# PIC795_Brain_Board.net
KiCad netlist of a schematic drawn in EAGLE
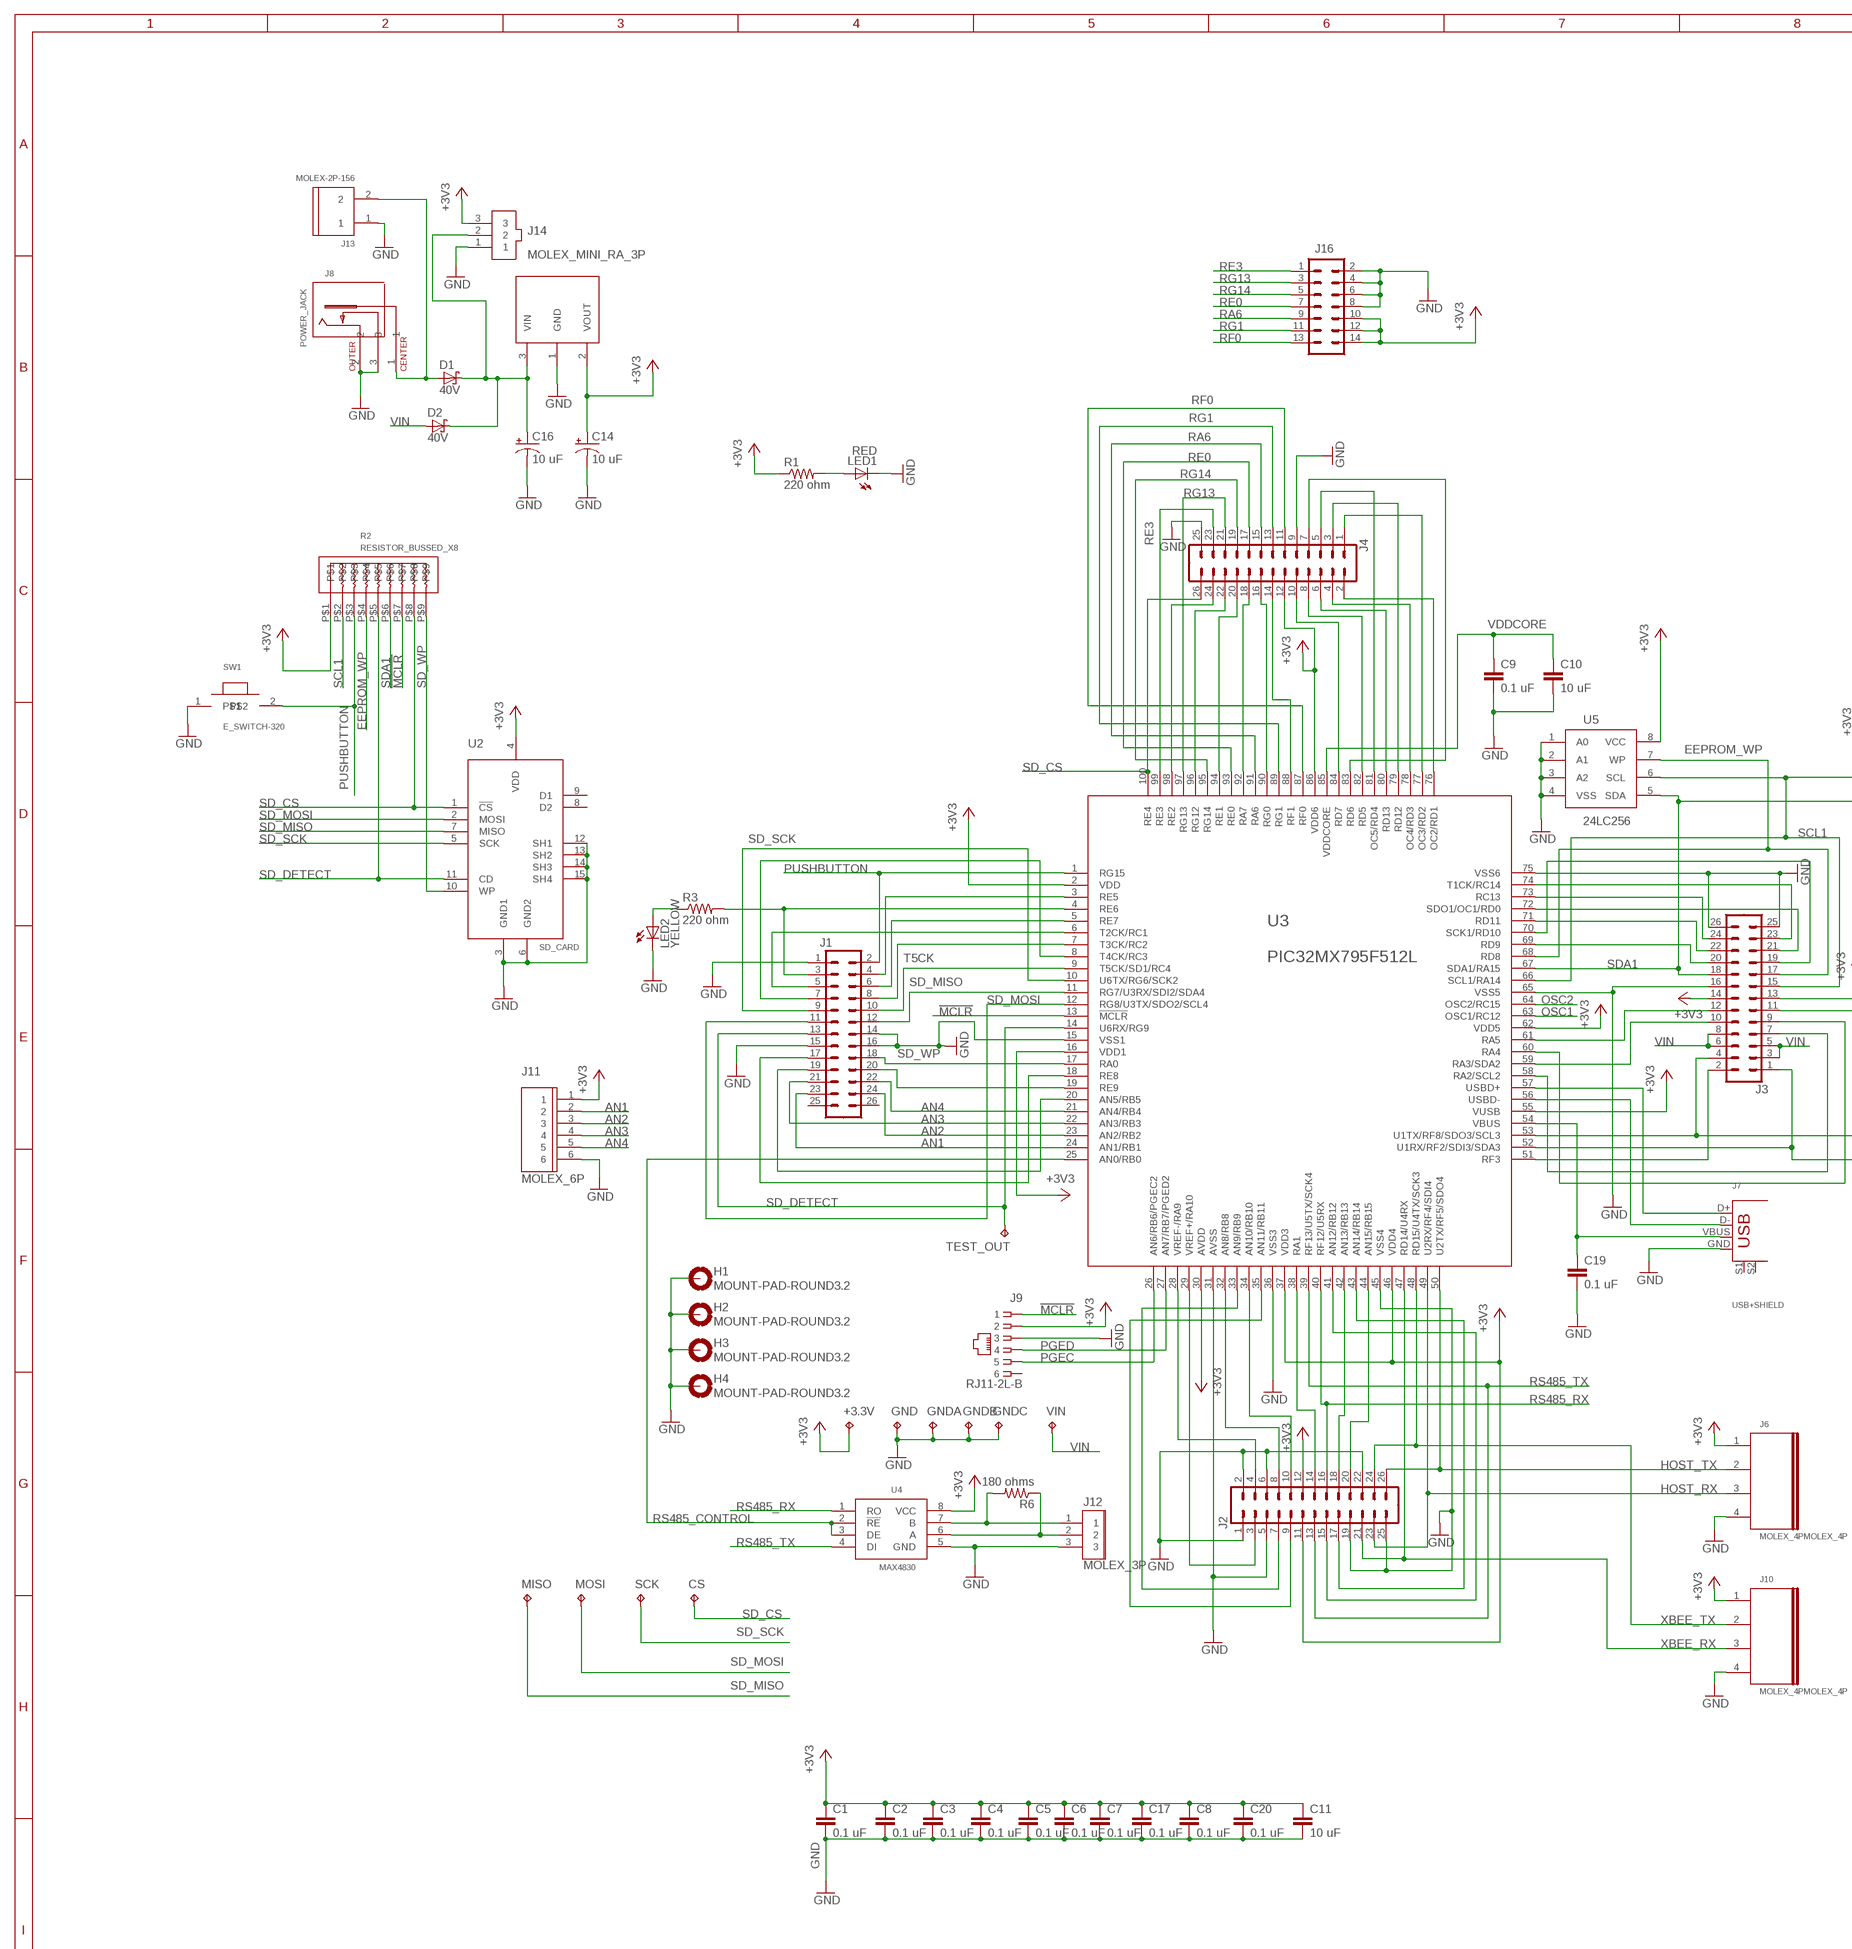
[diagram p0: schematic, sheet 1, part 1 of 2]
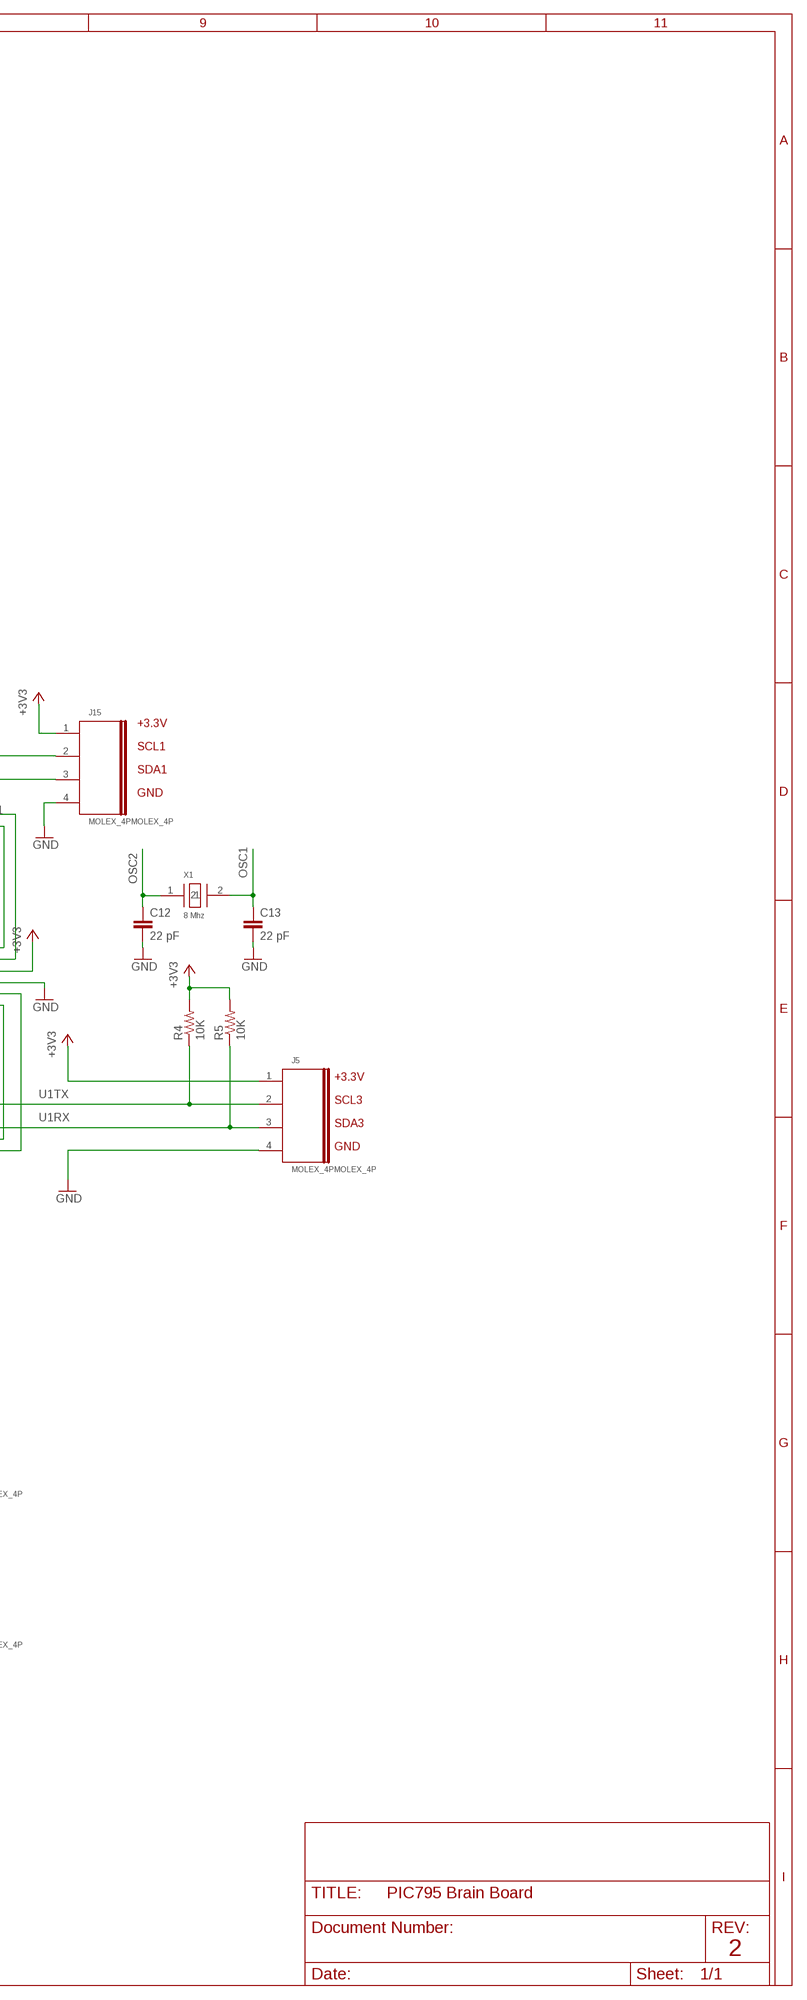
[diagram p1: schematic, sheet 1, part 2 of 2]

(export (version "E")
  (design (tool "Eeschema 10.0.6"))
  (components
    (comp (ref "+3.3V")
      (value "TP")
      (footprint "eagle-import:TESTPAD")
      (libsource (lib "eagle-import") (part "TP"))
    )
    (comp (ref "C1")
      (value "0.1 uF")
      (footprint "eagle-import:1206")
      (libsource (lib "eagle-import") (part "CAP-1206"))
    )
    (comp (ref "C2")
      (value "0.1 uF")
      (footprint "eagle-import:1206")
      (libsource (lib "eagle-import") (part "CAP-1206"))
    )
    (comp (ref "C3")
      (value "0.1 uF")
      (footprint "eagle-import:1206")
      (libsource (lib "eagle-import") (part "CAP-1206"))
    )
    (comp (ref "C4")
      (value "0.1 uF")
      (footprint "eagle-import:1206")
      (libsource (lib "eagle-import") (part "CAP-1206"))
    )
    (comp (ref "C5")
      (value "0.1 uF")
      (footprint "eagle-import:1206")
      (libsource (lib "eagle-import") (part "CAP-1206"))
    )
    (comp (ref "C6")
      (value "0.1 uF")
      (footprint "eagle-import:1206")
      (libsource (lib "eagle-import") (part "CAP-1206"))
    )
    (comp (ref "C7")
      (value "0.1 uF")
      (footprint "eagle-import:1206")
      (libsource (lib "eagle-import") (part "CAP-1206"))
    )
    (comp (ref "C8")
      (value "0.1 uF")
      (footprint "eagle-import:1206")
      (libsource (lib "eagle-import") (part "CAP-1206"))
    )
    (comp (ref "C9")
      (value "0.1 uF")
      (footprint "eagle-import:1206")
      (libsource (lib "eagle-import") (part "CAP-1206"))
    )
    (comp (ref "C10")
      (value "10 uF")
      (footprint "eagle-import:1206")
      (libsource (lib "eagle-import") (part "CAP-1206"))
    )
    (comp (ref "C11")
      (value "10 uF")
      (footprint "eagle-import:1206")
      (libsource (lib "eagle-import") (part "CAP-1206"))
    )
    (comp (ref "C12")
      (value "22 pF")
      (footprint "eagle-import:C0805")
      (libsource (lib "eagle-import") (part "C0805"))
    )
    (comp (ref "C13")
      (value "22 pF")
      (footprint "eagle-import:C0805")
      (libsource (lib "eagle-import") (part "C0805"))
    )
    (comp (ref "C14")
      (value "10 uF")
      (footprint "eagle-import:E2,5-5")
      (libsource (lib "eagle-import") (part "POLCAPE2.5-5"))
    )
    (comp (ref "C16")
      (value "10 uF")
      (footprint "eagle-import:E2,5-5")
      (libsource (lib "eagle-import") (part "POLCAPE2.5-5"))
    )
    (comp (ref "C17")
      (value "0.1 uF")
      (footprint "eagle-import:1206")
      (libsource (lib "eagle-import") (part "CAP-1206"))
    )
    (comp (ref "C19")
      (value "0.1 uF")
      (footprint "eagle-import:C5B2.5")
      (libsource (lib "eagle-import") (part "C5/2.5"))
    )
    (comp (ref "C20")
      (value "0.1 uF")
      (footprint "eagle-import:C5B2.5")
      (libsource (lib "eagle-import") (part "C5/2.5"))
    )
    (comp (ref "CS")
      (value "TP")
      (footprint "eagle-import:TESTPAD")
      (libsource (lib "eagle-import") (part "TP"))
    )
    (comp (ref "D1")
      (value "40V")
      (footprint "eagle-import:DO41-7.6")
      (libsource (lib "eagle-import") (part "1N5817-B"))
    )
    (comp (ref "D2")
      (value "40V")
      (footprint "eagle-import:DO41-7.6")
      (libsource (lib "eagle-import") (part "1N5817-B"))
    )
    (comp (ref "GND")
      (value "TP")
      (footprint "eagle-import:TESTPAD")
      (libsource (lib "eagle-import") (part "TP"))
    )
    (comp (ref "GNDA")
      (value "TP")
      (footprint "eagle-import:TESTPAD")
      (libsource (lib "eagle-import") (part "TP"))
    )
    (comp (ref "GNDB")
      (value "TP")
      (footprint "eagle-import:TESTPAD")
      (libsource (lib "eagle-import") (part "TP"))
    )
    (comp (ref "GNDC")
      (value "TP")
      (footprint "eagle-import:TESTPAD")
      (libsource (lib "eagle-import") (part "TP"))
    )
    (comp (ref "H1")
      (value "MOUNT-PAD-ROUND3.2")
      (footprint "eagle-import:3,2-PAD")
      (libsource (lib "eagle-import") (part "MOUNT-PAD-ROUND3.2"))
    )
    (comp (ref "H2")
      (value "MOUNT-PAD-ROUND3.2")
      (footprint "eagle-import:3,2-PAD")
      (libsource (lib "eagle-import") (part "MOUNT-PAD-ROUND3.2"))
    )
    (comp (ref "H3")
      (value "MOUNT-PAD-ROUND3.2")
      (footprint "eagle-import:3,2-PAD")
      (libsource (lib "eagle-import") (part "MOUNT-PAD-ROUND3.2"))
    )
    (comp (ref "H4")
      (value "MOUNT-PAD-ROUND3.2")
      (footprint "eagle-import:3,2-PAD")
      (libsource (lib "eagle-import") (part "MOUNT-PAD-ROUND3.2"))
    )
    (comp (ref "J1")
      (value "M13X22X13")
      (footprint "eagle-import:2X13")
      (libsource (lib "eagle-import") (part "M13X22X13"))
    )
    (comp (ref "J2")
      (value "M13X22X13")
      (footprint "eagle-import:2X13")
      (libsource (lib "eagle-import") (part "M13X22X13"))
    )
    (comp (ref "J3")
      (value "M13X22X13")
      (footprint "eagle-import:2X13")
      (libsource (lib "eagle-import") (part "M13X22X13"))
    )
    (comp (ref "J4")
      (value "M13X22X13")
      (footprint "eagle-import:2X13")
      (libsource (lib "eagle-import") (part "M13X22X13"))
    )
    (comp (ref "J5")
      (value "MOLEX_4PMOLEX_4P")
      (footprint "eagle-import:MOLEX_4P")
      (libsource (lib "eagle-import") (part "MOLEX_4PMOLEX_4P"))
    )
    (comp (ref "J6")
      (value "MOLEX_4PMOLEX_4P")
      (footprint "eagle-import:MOLEX_4P")
      (libsource (lib "eagle-import") (part "MOLEX_4PMOLEX_4P"))
    )
    (comp (ref "J7")
      (value "USB+SHIELD")
      (footprint "eagle-import:USB-B-PTH")
      (libsource (lib "eagle-import") (part "USB+SHIELD"))
    )
    (comp (ref "J8")
      (value "POWER_JACK")
      (footprint "eagle-import:POWER_JACK_PJ-202A")
      (libsource (lib "eagle-import") (part "POWER_JACK"))
    )
    (comp (ref "J9")
      (value "RJ11-2L-B")
      (footprint "eagle-import:RJ11-NO_SHIELD")
      (fields (field (name "MF") "TYCO ELECTRONICS"))
      (libsource (lib "eagle-import") (part "RJ11-2L-B"))
    )
    (comp (ref "J10")
      (value "MOLEX_4PMOLEX_4P")
      (footprint "eagle-import:MOLEX_4P")
      (libsource (lib "eagle-import") (part "MOLEX_4PMOLEX_4P"))
    )
    (comp (ref "J11")
      (value "MOLEX_6P")
      (footprint "eagle-import:MOLEX_6P_SLIM")
      (libsource (lib "eagle-import") (part "MOLEX_6P"))
    )
    (comp (ref "J12")
      (value "MOLEX_3P")
      (footprint "eagle-import:MOLEX_3P")
      (libsource (lib "eagle-import") (part "MOLEX_3P"))
    )
    (comp (ref "J13")
      (value "MOLEX-2P-156")
      (footprint "eagle-import:MOLEX-156-2P")
      (libsource (lib "eagle-import") (part "MOLEX-2P-156"))
    )
    (comp (ref "J14")
      (value "MOLEX_MINI_RA_3P")
      (footprint "eagle-import:MOLEX_MINI_RA_3P")
      (libsource (lib "eagle-import") (part "MOLEX_MINI_RA_3P"))
    )
    (comp (ref "J15")
      (value "MOLEX_4PMOLEX_4P")
      (footprint "eagle-import:MOLEX_4P")
      (libsource (lib "eagle-import") (part "MOLEX_4PMOLEX_4P"))
    )
    (comp (ref "J16")
      (value "CONNECTOR_DUAL_ROW_14")
      (footprint "eagle-import:2X7")
      (libsource (lib "eagle-import") (part "CONNECTOR_DUAL_ROW_14"))
    )
    (comp (ref "LED1")
      (value "RED")
      (footprint "eagle-import:LED5MM")
      (libsource (lib "eagle-import") (part "LED5MM"))
    )
    (comp (ref "LED2")
      (value "YELLOW")
      (footprint "eagle-import:LED5MM")
      (libsource (lib "eagle-import") (part "LED5MM"))
    )
    (comp (ref "MISO")
      (value "TP")
      (footprint "eagle-import:TESTPAD")
      (libsource (lib "eagle-import") (part "TP"))
    )
    (comp (ref "MOSI")
      (value "TP")
      (footprint "eagle-import:TESTPAD")
      (libsource (lib "eagle-import") (part "TP"))
    )
    (comp (ref "R1")
      (value "220 ohm")
      (footprint "eagle-import:1_4_WATT")
      (libsource (lib "eagle-import") (part "RESISTOR0207/12"))
    )
    (comp (ref "R2")
      (value "RESISTOR_BUSSED_X8")
      (footprint "eagle-import:RESISTOR_BUSSED")
      (libsource (lib "eagle-import") (part "RESISTOR_BUSSED_X8"))
    )
    (comp (ref "R3")
      (value "220 ohm")
      (footprint "eagle-import:1_4_WATT")
      (libsource (lib "eagle-import") (part "RESISTOR0207/12"))
    )
    (comp (ref "R4")
      (value "10K")
      (footprint "eagle-import:1_4_WATT")
      (libsource (lib "eagle-import") (part "RESISTOR0207/12"))
    )
    (comp (ref "R5")
      (value "10K")
      (footprint "eagle-import:1_4_WATT")
      (libsource (lib "eagle-import") (part "RESISTOR0207/12"))
    )
    (comp (ref "R6")
      (value "180 ohms")
      (footprint "eagle-import:0204_7")
      (libsource (lib "eagle-import") (part "RESISTOR0204/7"))
    )
    (comp (ref "SCK")
      (value "TP")
      (footprint "eagle-import:TESTPAD")
      (libsource (lib "eagle-import") (part "TP"))
    )
    (comp (ref "SW1")
      (value "E_SWITCH-320")
      (footprint "eagle-import:E_SWITCH_320")
      (libsource (lib "eagle-import") (part "E_SWITCH-320"))
    )
    (comp (ref "TEST_OUT")
      (value "TP")
      (footprint "eagle-import:TESTPAD")
      (libsource (lib "eagle-import") (part "TP"))
    )
    (comp (ref "U1")
      (value "REGULATOR_LD1086_LDO")
      (footprint "eagle-import:D2PAK")
      (libsource (lib "eagle-import") (part "REGULATOR_LD1086_LDO"))
    )
    (comp (ref "U2")
      (value "SD_CARD")
      (footprint "eagle-import:SD_CARD_TE_2041021")
      (libsource (lib "eagle-import") (part "SD_CARD"))
    )
    (comp (ref "U3")
      (value "PIC32MX795F512L")
      (footprint "eagle-import:TQFP-100-14X14MM")
      (libsource (lib "eagle-import") (part "PIC32MX795F512L"))
    )
    (comp (ref "U4")
      (value "MAX4830")
      (footprint "eagle-import:SOICN")
      (libsource (lib "eagle-import") (part "MAX485"))
    )
    (comp (ref "U5")
      (value "24LC256")
      (footprint "eagle-import:DIL08")
      (libsource (lib "eagle-import") (part "EEPROM_24LC256"))
    )
    (comp (ref "VIN")
      (value "TP")
      (footprint "eagle-import:TESTPAD")
      (libsource (lib "eagle-import") (part "TP"))
    )
    (comp (ref "X1")
      (value "8 Mhz")
      (footprint "eagle-import:CRYSTAL-SMD")
      (libsource (lib "eagle-import") (part "CRYSTAL-SMD"))
    )
  )
  (nets
    (net (code "1") (name "+3V3") (class "Default")
      (node (ref "+3.3V") (pin "P$1") (pinfunction "TP_P$1") (pintype "input"))
      (node (ref "C1") (pin "A") (pinfunction "1_A") (pintype "passive"))
      (node (ref "C11") (pin "A") (pinfunction "1_A") (pintype "passive"))
      (node (ref "C14") (pin "+") (pinfunction "+_+") (pintype "passive"))
      (node (ref "C17") (pin "A") (pinfunction "1_A") (pintype "passive"))
      (node (ref "C2") (pin "A") (pinfunction "1_A") (pintype "passive"))
      (node (ref "C20") (pin "1") (pinfunction "1_1") (pintype "passive"))
      (node (ref "C3") (pin "A") (pinfunction "1_A") (pintype "passive"))
      (node (ref "C4") (pin "A") (pinfunction "1_A") (pintype "passive"))
      (node (ref "C5") (pin "A") (pinfunction "1_A") (pintype "passive"))
      (node (ref "C6") (pin "A") (pinfunction "1_A") (pintype "passive"))
      (node (ref "C7") (pin "A") (pinfunction "1_A") (pintype "passive"))
      (node (ref "C8") (pin "A") (pinfunction "1_A") (pintype "passive"))
      (node (ref "J10") (pin "1") (pinfunction "1_1") (pintype "bidirectional"))
      (node (ref "J11") (pin "1") (pinfunction "1_1") (pintype "bidirectional"))
      (node (ref "J14") (pin "3") (pinfunction "3_3") (pintype "bidirectional"))
      (node (ref "J15") (pin "1") (pinfunction "1_1") (pintype "bidirectional"))
      (node (ref "J16") (pin "10") (pinfunction "10_10") (pintype "passive"))
      (node (ref "J16") (pin "12") (pinfunction "12_12") (pintype "passive"))
      (node (ref "J16") (pin "14") (pinfunction "14_14") (pintype "passive"))
      (node (ref "J2") (pin "11") (pinfunction "11_11") (pintype "passive"))
      (node (ref "J2") (pin "12") (pinfunction "12_12") (pintype "passive"))
      (node (ref "J3") (pin "13") (pinfunction "13_13") (pintype "passive"))
      (node (ref "J3") (pin "14") (pinfunction "14_14") (pintype "passive"))
      (node (ref "J4") (pin "12") (pinfunction "12_12") (pintype "passive"))
      (node (ref "J5") (pin "1") (pinfunction "1_1") (pintype "bidirectional"))
      (node (ref "J6") (pin "1") (pinfunction "1_1") (pintype "bidirectional"))
      (node (ref "J9") (pin "2") (pinfunction "2_2") (pintype "passive"))
      (node (ref "R1") (pin "1") (pinfunction "1_1") (pintype "passive"))
      (node (ref "R2") (pin "P$1") (pinfunction "P$1_P$1") (pintype "bidirectional"))
      (node (ref "R4") (pin "2") (pinfunction "2_2") (pintype "passive"))
      (node (ref "R5") (pin "2") (pinfunction "2_2") (pintype "passive"))
      (node (ref "U1") (pin "2") (pinfunction "VOUT_2") (pintype "bidirectional"))
      (node (ref "U2") (pin "4") (pinfunction "VDD_4") (pintype "bidirectional"))
      (node (ref "U3") (pin "16") (pinfunction "VDD1_16") (pintype "bidirectional"))
      (node (ref "U3") (pin "2") (pinfunction "VDD_2") (pintype "bidirectional"))
      (node (ref "U3") (pin "30") (pinfunction "AVDD_30") (pintype "bidirectional"))
      (node (ref "U3") (pin "37") (pinfunction "VDD3_37") (pintype "bidirectional"))
      (node (ref "U3") (pin "46") (pinfunction "VDD4_46") (pintype "bidirectional"))
      (node (ref "U3") (pin "55") (pinfunction "VUSB_55") (pintype "bidirectional"))
      (node (ref "U3") (pin "62") (pinfunction "VDD5_62") (pintype "bidirectional"))
      (node (ref "U3") (pin "86") (pinfunction "VDD6_86") (pintype "bidirectional"))
      (node (ref "U4") (pin "8") (pinfunction "VCC_8") (pintype "power_in"))
      (node (ref "U5") (pin "8") (pinfunction "VCC_8") (pintype "bidirectional"))
    )
    (net (code "2") (name "/AN1") (class "Default")
      (node (ref "J1") (pin "23") (pinfunction "23_23") (pintype "passive"))
      (node (ref "J11") (pin "2") (pinfunction "2_2") (pintype "bidirectional"))
      (node (ref "U3") (pin "24") (pinfunction "AN1/RB1_24") (pintype "bidirectional"))
    )
    (net (code "3") (name "/AN2") (class "Default")
      (node (ref "J1") (pin "24") (pinfunction "24_24") (pintype "passive"))
      (node (ref "J11") (pin "3") (pinfunction "3_3") (pintype "bidirectional"))
      (node (ref "U3") (pin "23") (pinfunction "AN2/RB2_23") (pintype "bidirectional"))
    )
    (net (code "4") (name "/AN3") (class "Default")
      (node (ref "J1") (pin "21") (pinfunction "21_21") (pintype "passive"))
      (node (ref "J11") (pin "4") (pinfunction "4_4") (pintype "bidirectional"))
      (node (ref "U3") (pin "22") (pinfunction "AN3/RB3_22") (pintype "bidirectional"))
    )
    (net (code "5") (name "/AN4") (class "Default")
      (node (ref "J1") (pin "22") (pinfunction "22_22") (pintype "passive"))
      (node (ref "J11") (pin "5") (pinfunction "5_5") (pintype "bidirectional"))
      (node (ref "U3") (pin "21") (pinfunction "AN4/RB4_21") (pintype "bidirectional"))
    )
    (net (code "6") (name "/EEPROM_WP") (class "Default")
      (node (ref "J3") (pin "17") (pinfunction "17_17") (pintype "passive"))
      (node (ref "R2") (pin "P$4") (pinfunction "P$4_P$4") (pintype "bidirectional"))
      (node (ref "U3") (pin "68") (pinfunction "RD8_68") (pintype "bidirectional"))
      (node (ref "U5") (pin "7") (pinfunction "WP_7") (pintype "bidirectional"))
    )
    (net (code "7") (name "/HOST_RX") (class "Default")
      (node (ref "J2") (pin "23") (pinfunction "23_23") (pintype "passive"))
      (node (ref "J6") (pin "3") (pinfunction "3_3") (pintype "bidirectional"))
      (node (ref "U3") (pin "49") (pinfunction "U2RX/RF4/SDI4_49") (pintype "bidirectional"))
    )
    (net (code "8") (name "/HOST_TX") (class "Default")
      (node (ref "J2") (pin "26") (pinfunction "26_26") (pintype "passive"))
      (node (ref "J6") (pin "2") (pinfunction "2_2") (pintype "bidirectional"))
      (node (ref "U3") (pin "50") (pinfunction "U2TX/RF5/SDO4_50") (pintype "bidirectional"))
    )
    (net (code "9") (name "/OSC1") (class "Default")
      (node (ref "C13") (pin "1") (pinfunction "1_1") (pintype "passive"))
      (node (ref "U3") (pin "63") (pinfunction "OSC1/RC12_63") (pintype "bidirectional"))
      (node (ref "X1") (pin "2") (pinfunction "2_2") (pintype "bidirectional"))
    )
    (net (code "10") (name "/OSC2") (class "Default")
      (node (ref "C12") (pin "1") (pinfunction "1_1") (pintype "passive"))
      (node (ref "U3") (pin "64") (pinfunction "OSC2/RC15_64") (pintype "bidirectional"))
      (node (ref "X1") (pin "1") (pinfunction "1_1") (pintype "bidirectional"))
    )
    (net (code "11") (name "/PGEC") (class "Default")
      (node (ref "J9") (pin "5") (pinfunction "5_5") (pintype "passive"))
      (node (ref "U3") (pin "26") (pinfunction "AN6/RB6/PGEC2_26") (pintype "bidirectional"))
    )
    (net (code "12") (name "/PGED") (class "Default")
      (node (ref "J9") (pin "4") (pinfunction "4_4") (pintype "passive"))
      (node (ref "U3") (pin "27") (pinfunction "AN7/RB7/PGED2_27") (pintype "bidirectional"))
    )
    (net (code "13") (name "/PUSHBUTTON") (class "Default")
      (node (ref "J1") (pin "2") (pinfunction "2_2") (pintype "passive"))
      (node (ref "R2") (pin "P$3") (pinfunction "P$3_P$3") (pintype "bidirectional"))
      (node (ref "SW1") (pin "2") (pinfunction "P$2_2") (pintype "bidirectional"))
      (node (ref "U3") (pin "1") (pinfunction "RG15_1") (pintype "bidirectional"))
    )
    (net (code "14") (name "/RA6") (class "Default")
      (node (ref "J16") (pin "9") (pinfunction "9_9") (pintype "passive"))
      (node (ref "J4") (pin "15") (pinfunction "15_15") (pintype "passive"))
      (node (ref "U3") (pin "91") (pinfunction "RA6_91") (pintype "bidirectional"))
    )
    (net (code "15") (name "/RE0") (class "Default")
      (node (ref "J16") (pin "7") (pinfunction "7_7") (pintype "passive"))
      (node (ref "J4") (pin "17") (pinfunction "17_17") (pintype "passive"))
      (node (ref "U3") (pin "93") (pinfunction "RE0_93") (pintype "bidirectional"))
    )
    (net (code "16") (name "/RE3") (class "Default")
      (node (ref "J16") (pin "1") (pinfunction "1_1") (pintype "passive"))
      (node (ref "J4") (pin "23") (pinfunction "23_23") (pintype "passive"))
      (node (ref "U3") (pin "99") (pinfunction "RE3_99") (pintype "bidirectional"))
    )
    (net (code "17") (name "/RF0") (class "Default")
      (node (ref "J16") (pin "13") (pinfunction "13_13") (pintype "passive"))
      (node (ref "J4") (pin "11") (pinfunction "11_11") (pintype "passive"))
      (node (ref "U3") (pin "87") (pinfunction "RF0_87") (pintype "bidirectional"))
    )
    (net (code "18") (name "/RG1") (class "Default")
      (node (ref "J16") (pin "11") (pinfunction "11_11") (pintype "passive"))
      (node (ref "J4") (pin "13") (pinfunction "13_13") (pintype "passive"))
      (node (ref "U3") (pin "89") (pinfunction "RG1_89") (pintype "bidirectional"))
    )
    (net (code "19") (name "/RG13") (class "Default")
      (node (ref "J16") (pin "3") (pinfunction "3_3") (pintype "passive"))
      (node (ref "J4") (pin "21") (pinfunction "21_21") (pintype "passive"))
      (node (ref "U3") (pin "97") (pinfunction "RG13_97") (pintype "bidirectional"))
    )
    (net (code "20") (name "/RG14") (class "Default")
      (node (ref "J16") (pin "5") (pinfunction "5_5") (pintype "passive"))
      (node (ref "J4") (pin "19") (pinfunction "19_19") (pintype "passive"))
      (node (ref "U3") (pin "95") (pinfunction "RG14_95") (pintype "bidirectional"))
    )
    (net (code "21") (name "/RS485_CONTROL") (class "Default")
      (node (ref "U3") (pin "25") (pinfunction "AN0/RB0_25") (pintype "bidirectional"))
      (node (ref "U4") (pin "2") (pinfunction "~{RE}_2") (pintype "input"))
      (node (ref "U4") (pin "3") (pinfunction "DE_3") (pintype "input"))
    )
    (net (code "22") (name "/RS485_RX") (class "Default")
      (node (ref "J2") (pin "16") (pinfunction "16_16") (pintype "passive"))
      (node (ref "U3") (pin "40") (pinfunction "RF12/U5RX_40") (pintype "bidirectional"))
      (node (ref "U4") (pin "1") (pinfunction "RO_1") (pintype "output"))
    )
    (net (code "23") (name "/RS485_TX") (class "Default")
      (node (ref "J2") (pin "13") (pinfunction "13_13") (pintype "passive"))
      (node (ref "U3") (pin "39") (pinfunction "RF13/U5TX/SCK4_39") (pintype "bidirectional"))
      (node (ref "U4") (pin "4") (pinfunction "DI_4") (pintype "input"))
    )
    (net (code "24") (name "/SCL1") (class "Default")
      (node (ref "J15") (pin "2") (pinfunction "2_2") (pintype "bidirectional"))
      (node (ref "J3") (pin "15") (pinfunction "15_15") (pintype "passive"))
      (node (ref "R2") (pin "P$2") (pinfunction "P$2_P$2") (pintype "bidirectional"))
      (node (ref "U3") (pin "66") (pinfunction "SCL1/RA14_66") (pintype "bidirectional"))
      (node (ref "U5") (pin "6") (pinfunction "SCL_6") (pintype "bidirectional"))
    )
    (net (code "25") (name "/SDA1") (class "Default")
      (node (ref "J15") (pin "3") (pinfunction "3_3") (pintype "bidirectional"))
      (node (ref "J3") (pin "18") (pinfunction "18_18") (pintype "passive"))
      (node (ref "R2") (pin "P$6") (pinfunction "P$6_P$6") (pintype "bidirectional"))
      (node (ref "U3") (pin "67") (pinfunction "SDA1/RA15_67") (pintype "bidirectional"))
      (node (ref "U5") (pin "5") (pinfunction "SDA_5") (pintype "bidirectional"))
    )
    (net (code "26") (name "/SD_CS") (class "Default")
      (node (ref "CS") (pin "P$1") (pinfunction "TP_P$1") (pintype "input"))
      (node (ref "J4") (pin "26") (pinfunction "26_26") (pintype "passive"))
      (node (ref "R2") (pin "P$8") (pinfunction "P$8_P$8") (pintype "bidirectional"))
      (node (ref "U2") (pin "1") (pinfunction "~{CS}_1") (pintype "bidirectional"))
      (node (ref "U3") (pin "100") (pinfunction "RE4_100") (pintype "bidirectional"))
    )
    (net (code "27") (name "/SD_DETECT") (class "Default")
      (node (ref "J1") (pin "13") (pinfunction "13_13") (pintype "passive"))
      (node (ref "R2") (pin "P$5") (pinfunction "P$5_P$5") (pintype "bidirectional"))
      (node (ref "TEST_OUT") (pin "P$1") (pinfunction "TP_P$1") (pintype "input"))
      (node (ref "U2") (pin "11") (pinfunction "CD_11") (pintype "bidirectional"))
      (node (ref "U3") (pin "14") (pinfunction "U6RX/RG9_14") (pintype "bidirectional"))
    )
    (net (code "28") (name "/SD_MISO") (class "Default")
      (node (ref "J1") (pin "12") (pinfunction "12_12") (pintype "passive"))
      (node (ref "MISO") (pin "P$1") (pinfunction "TP_P$1") (pintype "input"))
      (node (ref "U2") (pin "7") (pinfunction "MISO_7") (pintype "bidirectional"))
      (node (ref "U3") (pin "11") (pinfunction "RG7/U3RX/SDI2/SDA4_11") (pintype "bidirectional"))
    )
    (net (code "29") (name "/SD_MOSI") (class "Default")
      (node (ref "J1") (pin "11") (pinfunction "11_11") (pintype "passive"))
      (node (ref "MOSI") (pin "P$1") (pinfunction "TP_P$1") (pintype "input"))
      (node (ref "U2") (pin "2") (pinfunction "MOSI_2") (pintype "bidirectional"))
      (node (ref "U3") (pin "12") (pinfunction "RG8/U3TX/SDO2/SCL4_12") (pintype "bidirectional"))
    )
    (net (code "30") (name "/SD_SCK") (class "Default")
      (node (ref "J1") (pin "9") (pinfunction "9_9") (pintype "passive"))
      (node (ref "SCK") (pin "P$1") (pinfunction "TP_P$1") (pintype "input"))
      (node (ref "U2") (pin "5") (pinfunction "SCK_5") (pintype "bidirectional"))
      (node (ref "U3") (pin "10") (pinfunction "U6TX/RG6/SCK2_10") (pintype "bidirectional"))
    )
    (net (code "31") (name "/SD_WP") (class "Default")
      (node (ref "J1") (pin "18") (pinfunction "18_18") (pintype "passive"))
      (node (ref "R2") (pin "P$9") (pinfunction "P$9_P$9") (pintype "bidirectional"))
      (node (ref "U2") (pin "10") (pinfunction "WP_10") (pintype "bidirectional"))
      (node (ref "U3") (pin "17") (pinfunction "RA0_17") (pintype "bidirectional"))
    )
    (net (code "32") (name "/T5CK") (class "Default")
      (node (ref "J1") (pin "10") (pinfunction "10_10") (pintype "passive"))
      (node (ref "U3") (pin "9") (pinfunction "T5CK/SD1/RC4_9") (pintype "bidirectional"))
    )
    (net (code "33") (name "/U1RX") (class "Default")
      (node (ref "J3") (pin "1") (pinfunction "1_1") (pintype "passive"))
      (node (ref "J5") (pin "3") (pinfunction "3_3") (pintype "bidirectional"))
      (node (ref "R5") (pin "1") (pinfunction "1_1") (pintype "passive"))
      (node (ref "U3") (pin "52") (pinfunction "U1RX/RF2/SDI3/SDA3_52") (pintype "bidirectional"))
    )
    (net (code "34") (name "/U1TX") (class "Default")
      (node (ref "J3") (pin "4") (pinfunction "4_4") (pintype "passive"))
      (node (ref "J5") (pin "2") (pinfunction "2_2") (pintype "bidirectional"))
      (node (ref "R4") (pin "1") (pinfunction "1_1") (pintype "passive"))
      (node (ref "U3") (pin "53") (pinfunction "U1TX/RF8/SDO3/SCL3_53") (pintype "bidirectional"))
    )
    (net (code "35") (name "/VDDCORE") (class "Default")
      (node (ref "C10") (pin "A") (pinfunction "1_A") (pintype "passive"))
      (node (ref "C9") (pin "A") (pinfunction "1_A") (pintype "passive"))
      (node (ref "U3") (pin "85") (pinfunction "VDDCORE_85") (pintype "bidirectional"))
    )
    (net (code "36") (name "/VIN") (class "Default")
      (node (ref "D2") (pin "A") (pinfunction "A_A") (pintype "passive"))
      (node (ref "J3") (pin "3") (pinfunction "3_3") (pintype "passive"))
      (node (ref "J3") (pin "5") (pinfunction "5_5") (pintype "passive"))
      (node (ref "J3") (pin "6") (pinfunction "6_6") (pintype "passive"))
      (node (ref "J3") (pin "8") (pinfunction "8_8") (pintype "passive"))
      (node (ref "VIN") (pin "P$1") (pinfunction "TP_P$1") (pintype "input"))
    )
    (net (code "37") (name "/XBEE_RX") (class "Default")
      (node (ref "J10") (pin "3") (pinfunction "3_3") (pintype "bidirectional"))
      (node (ref "J2") (pin "21") (pinfunction "21_21") (pintype "passive"))
      (node (ref "U3") (pin "47") (pinfunction "RD14/U4RX_47") (pintype "bidirectional"))
    )
    (net (code "38") (name "/XBEE_TX") (class "Default")
      (node (ref "J10") (pin "2") (pinfunction "2_2") (pintype "bidirectional"))
      (node (ref "J2") (pin "24") (pinfunction "24_24") (pintype "passive"))
      (node (ref "U3") (pin "48") (pinfunction "RD15/U4TX/SCK3_48") (pintype "bidirectional"))
    )
    (net (code "39") (name "/~{MCLR}") (class "Default")
      (node (ref "J9") (pin "1") (pinfunction "1_1") (pintype "passive"))
      (node (ref "R2") (pin "P$7") (pinfunction "P$7_P$7") (pintype "bidirectional"))
      (node (ref "U3") (pin "13") (pinfunction "~{MCLR}_13") (pintype "bidirectional"))
    )
    (net (code "40") (name "GND") (class "Default")
      (node (ref "C1") (pin "C") (pinfunction "2_C") (pintype "passive"))
      (node (ref "C10") (pin "C") (pinfunction "2_C") (pintype "passive"))
      (node (ref "C11") (pin "C") (pinfunction "2_C") (pintype "passive"))
      (node (ref "C12") (pin "2") (pinfunction "2_2") (pintype "passive"))
      (node (ref "C13") (pin "2") (pinfunction "2_2") (pintype "passive"))
      (node (ref "C14") (pin "-") (pinfunction "-_-") (pintype "passive"))
      (node (ref "C16") (pin "-") (pinfunction "-_-") (pintype "passive"))
      (node (ref "C17") (pin "C") (pinfunction "2_C") (pintype "passive"))
      (node (ref "C19") (pin "2") (pinfunction "2_2") (pintype "passive"))
      (node (ref "C2") (pin "C") (pinfunction "2_C") (pintype "passive"))
      (node (ref "C20") (pin "2") (pinfunction "2_2") (pintype "passive"))
      (node (ref "C3") (pin "C") (pinfunction "2_C") (pintype "passive"))
      (node (ref "C4") (pin "C") (pinfunction "2_C") (pintype "passive"))
      (node (ref "C5") (pin "C") (pinfunction "2_C") (pintype "passive"))
      (node (ref "C6") (pin "C") (pinfunction "2_C") (pintype "passive"))
      (node (ref "C7") (pin "C") (pinfunction "2_C") (pintype "passive"))
      (node (ref "C8") (pin "C") (pinfunction "2_C") (pintype "passive"))
      (node (ref "C9") (pin "C") (pinfunction "2_C") (pintype "passive"))
      (node (ref "GND") (pin "P$1") (pinfunction "TP_P$1") (pintype "input"))
      (node (ref "GNDA") (pin "P$1") (pinfunction "TP_P$1") (pintype "input"))
      (node (ref "GNDB") (pin "P$1") (pinfunction "TP_P$1") (pintype "input"))
      (node (ref "GNDC") (pin "P$1") (pinfunction "TP_P$1") (pintype "input"))
      (node (ref "H1") (pin "B3,2") (pinfunction "MOUNT_B3,2") (pintype "passive"))
      (node (ref "H2") (pin "B3,2") (pinfunction "MOUNT_B3,2") (pintype "passive"))
      (node (ref "H3") (pin "B3,2") (pinfunction "MOUNT_B3,2") (pintype "passive"))
      (node (ref "H4") (pin "B3,2") (pinfunction "MOUNT_B3,2") (pintype "passive"))
      (node (ref "J1") (pin "1") (pinfunction "1_1") (pintype "passive"))
      (node (ref "J1") (pin "14") (pinfunction "14_14") (pintype "passive"))
      (node (ref "J1") (pin "15") (pinfunction "15_15") (pintype "passive"))
      (node (ref "J1") (pin "16") (pinfunction "16_16") (pintype "passive"))
      (node (ref "J10") (pin "4") (pinfunction "4_4") (pintype "bidirectional"))
      (node (ref "J11") (pin "6") (pinfunction "6_6") (pintype "bidirectional"))
      (node (ref "J12") (pin "3") (pinfunction "3_3") (pintype "bidirectional"))
      (node (ref "J13") (pin "1") (pinfunction "1_1") (pintype "bidirectional"))
      (node (ref "J14") (pin "1") (pinfunction "1_1") (pintype "bidirectional"))
      (node (ref "J15") (pin "4") (pinfunction "4_4") (pintype "bidirectional"))
      (node (ref "J16") (pin "2") (pinfunction "2_2") (pintype "passive"))
      (node (ref "J16") (pin "4") (pinfunction "4_4") (pintype "passive"))
      (node (ref "J16") (pin "6") (pinfunction "6_6") (pintype "passive"))
      (node (ref "J16") (pin "8") (pinfunction "8_8") (pintype "passive"))
      (node (ref "J2") (pin "1") (pinfunction "1_1") (pintype "passive"))
      (node (ref "J2") (pin "19") (pinfunction "19_19") (pintype "passive"))
      (node (ref "J2") (pin "2") (pinfunction "2_2") (pintype "passive"))
      (node (ref "J2") (pin "22") (pinfunction "22_22") (pintype "passive"))
      (node (ref "J2") (pin "25") (pinfunction "25_25") (pintype "passive"))
      (node (ref "J2") (pin "5") (pinfunction "5_5") (pintype "passive"))
      (node (ref "J2") (pin "6") (pinfunction "6_6") (pintype "passive"))
      (node (ref "J3") (pin "11") (pinfunction "11_11") (pintype "passive"))
      (node (ref "J3") (pin "16") (pinfunction "16_16") (pintype "passive"))
      (node (ref "J3") (pin "25") (pinfunction "25_25") (pintype "passive"))
      (node (ref "J3") (pin "26") (pinfunction "26_26") (pintype "passive"))
      (node (ref "J4") (pin "25") (pinfunction "25_25") (pintype "passive"))
      (node (ref "J4") (pin "9") (pinfunction "9_9") (pintype "passive"))
      (node (ref "J5") (pin "4") (pinfunction "4_4") (pintype "bidirectional"))
      (node (ref "J6") (pin "4") (pinfunction "4_4") (pintype "bidirectional"))
      (node (ref "J7") (pin "GND") (pinfunction "GND_GND") (pintype "bidirectional"))
      (node (ref "J8") (pin "2") (pinfunction "2_2") (pintype "bidirectional"))
      (node (ref "J8") (pin "3") (pinfunction "3_3") (pintype "bidirectional"))
      (node (ref "J9") (pin "3") (pinfunction "3_3") (pintype "passive"))
      (node (ref "LED1") (pin "K") (pinfunction "C_K") (pintype "passive"))
      (node (ref "LED2") (pin "K") (pinfunction "C_K") (pintype "passive"))
      (node (ref "SW1") (pin "1") (pinfunction "P$1_1") (pintype "bidirectional"))
      (node (ref "U1") (pin "1") (pinfunction "GND_1") (pintype "bidirectional"))
      (node (ref "U2") (pin "12") (pinfunction "SH1_12") (pintype "bidirectional"))
      (node (ref "U2") (pin "13") (pinfunction "SH2_13") (pintype "bidirectional"))
      (node (ref "U2") (pin "14") (pinfunction "SH3_14") (pintype "bidirectional"))
      (node (ref "U2") (pin "15") (pinfunction "SH4_15") (pintype "bidirectional"))
      (node (ref "U2") (pin "3") (pinfunction "GND1_3") (pintype "bidirectional"))
      (node (ref "U2") (pin "6") (pinfunction "GND2_6") (pintype "bidirectional"))
      (node (ref "U3") (pin "15") (pinfunction "VSS1_15") (pintype "bidirectional"))
      (node (ref "U3") (pin "31") (pinfunction "AVSS_31") (pintype "bidirectional"))
      (node (ref "U3") (pin "36") (pinfunction "VSS3_36") (pintype "bidirectional"))
      (node (ref "U3") (pin "45") (pinfunction "VSS4_45") (pintype "bidirectional"))
      (node (ref "U3") (pin "65") (pinfunction "VSS5_65") (pintype "bidirectional"))
      (node (ref "U3") (pin "75") (pinfunction "VSS6_75") (pintype "bidirectional"))
      (node (ref "U4") (pin "5") (pinfunction "GND_5") (pintype "power_in"))
      (node (ref "U5") (pin "1") (pinfunction "A0_1") (pintype "bidirectional"))
      (node (ref "U5") (pin "2") (pinfunction "A1_2") (pintype "bidirectional"))
      (node (ref "U5") (pin "3") (pinfunction "A2_3") (pintype "bidirectional"))
      (node (ref "U5") (pin "4") (pinfunction "VSS_4") (pintype "bidirectional"))
    )
    (net (code "41") (name "Net-(D1-PadA)") (class "Default")
      (node (ref "D1") (pin "A") (pinfunction "A_A") (pintype "passive"))
      (node (ref "J13") (pin "2") (pinfunction "2_2") (pintype "bidirectional"))
      (node (ref "J8") (pin "1") (pinfunction "1_1") (pintype "bidirectional"))
    )
    (net (code "42") (name "Net-(LED1-PadA)") (class "Default")
      (node (ref "LED1") (pin "A") (pinfunction "A_A") (pintype "passive"))
      (node (ref "R1") (pin "2") (pinfunction "2_2") (pintype "passive"))
    )
    (net (code "43") (name "Net-(LED2-PadA)") (class "Default")
      (node (ref "LED2") (pin "A") (pinfunction "A_A") (pintype "passive"))
      (node (ref "R3") (pin "1") (pinfunction "1_1") (pintype "passive"))
    )
    (net (code "44") (name "Net-(U1-VIN)") (class "Default")
      (node (ref "C16") (pin "+") (pinfunction "+_+") (pintype "passive"))
      (node (ref "D1") (pin "C") (pinfunction "C_C") (pintype "passive"))
      (node (ref "D2") (pin "C") (pinfunction "C_C") (pintype "passive"))
      (node (ref "J14") (pin "2") (pinfunction "2_2") (pintype "bidirectional"))
      (node (ref "U1") (pin "3") (pinfunction "VIN_3") (pintype "bidirectional"))
    )
    (net (code "45") (name "Net-(U3-AN5{slash}RB5)") (class "Default")
      (node (ref "J1") (pin "19") (pinfunction "19_19") (pintype "passive"))
      (node (ref "U3") (pin "20") (pinfunction "AN5/RB5_20") (pintype "bidirectional"))
    )
    (net (code "46") (name "Net-(U3-AN8{slash}RB8)") (class "Default")
      (node (ref "J2") (pin "8") (pinfunction "8_8") (pintype "passive"))
      (node (ref "U3") (pin "32") (pinfunction "AN8/RB8_32") (pintype "bidirectional"))
    )
    (net (code "47") (name "Net-(U3-AN9{slash}RB9)") (class "Default")
      (node (ref "J2") (pin "7") (pinfunction "7_7") (pintype "passive"))
      (node (ref "U3") (pin "33") (pinfunction "AN9/RB9_33") (pintype "bidirectional"))
    )
    (net (code "48") (name "Net-(U3-AN10{slash}RB10)") (class "Default")
      (node (ref "J2") (pin "10") (pinfunction "10_10") (pintype "passive"))
      (node (ref "U3") (pin "34") (pinfunction "AN10/RB10_34") (pintype "bidirectional"))
    )
    (net (code "49") (name "Net-(U3-AN11{slash}RB11)") (class "Default")
      (node (ref "J2") (pin "9") (pinfunction "9_9") (pintype "passive"))
      (node (ref "U3") (pin "35") (pinfunction "AN11/RB11_35") (pintype "bidirectional"))
    )
    (net (code "50") (name "Net-(U3-AN12{slash}RB12)") (class "Default")
      (node (ref "J2") (pin "15") (pinfunction "15_15") (pintype "passive"))
      (node (ref "U3") (pin "41") (pinfunction "AN12/RB12_41") (pintype "bidirectional"))
    )
    (net (code "51") (name "Net-(U3-AN13{slash}RB13)") (class "Default")
      (node (ref "J2") (pin "18") (pinfunction "18_18") (pintype "passive"))
      (node (ref "U3") (pin "42") (pinfunction "AN13/RB13_42") (pintype "bidirectional"))
    )
    (net (code "52") (name "Net-(U3-AN14{slash}RB14)") (class "Default")
      (node (ref "J2") (pin "17") (pinfunction "17_17") (pintype "passive"))
      (node (ref "U3") (pin "43") (pinfunction "AN14/RB14_43") (pintype "bidirectional"))
    )
    (net (code "53") (name "Net-(U3-AN15{slash}RB15)") (class "Default")
      (node (ref "J2") (pin "20") (pinfunction "20_20") (pintype "passive"))
      (node (ref "U3") (pin "44") (pinfunction "AN15/RB15_44") (pintype "bidirectional"))
    )
    (net (code "54") (name "Net-(U3-OC2{slash}RD1)") (class "Default")
      (node (ref "J4") (pin "2") (pinfunction "2_2") (pintype "passive"))
      (node (ref "U3") (pin "76") (pinfunction "OC2/RD1_76") (pintype "bidirectional"))
    )
    (net (code "55") (name "Net-(U3-OC3{slash}RD2)") (class "Default")
      (node (ref "J4") (pin "1") (pinfunction "1_1") (pintype "passive"))
      (node (ref "U3") (pin "77") (pinfunction "OC3/RD2_77") (pintype "bidirectional"))
    )
    (net (code "56") (name "Net-(U3-OC4{slash}RD3)") (class "Default")
      (node (ref "J4") (pin "4") (pinfunction "4_4") (pintype "passive"))
      (node (ref "U3") (pin "78") (pinfunction "OC4/RD3_78") (pintype "bidirectional"))
    )
    (net (code "57") (name "Net-(U3-OC5{slash}RD4)") (class "Default")
      (node (ref "J4") (pin "5") (pinfunction "5_5") (pintype "passive"))
      (node (ref "U3") (pin "81") (pinfunction "OC5/RD4_81") (pintype "bidirectional"))
    )
    (net (code "58") (name "Net-(U3-RA1)") (class "Default")
      (node (ref "J2") (pin "14") (pinfunction "14_14") (pintype "passive"))
      (node (ref "U3") (pin "38") (pinfunction "RA1_38") (pintype "bidirectional"))
    )
    (net (code "59") (name "Net-(U3-RA2{slash}SCL2)") (class "Default")
      (node (ref "J3") (pin "7") (pinfunction "7_7") (pintype "passive"))
      (node (ref "U3") (pin "58") (pinfunction "RA2/SCL2_58") (pintype "bidirectional"))
    )
    (net (code "60") (name "Net-(U3-RA3{slash}SDA2)") (class "Default")
      (node (ref "J3") (pin "10") (pinfunction "10_10") (pintype "passive"))
      (node (ref "U3") (pin "59") (pinfunction "RA3/SDA2_59") (pintype "bidirectional"))
    )
    (net (code "61") (name "Net-(U3-RA4)") (class "Default")
      (node (ref "J3") (pin "9") (pinfunction "9_9") (pintype "passive"))
      (node (ref "U3") (pin "60") (pinfunction "RA4_60") (pintype "bidirectional"))
    )
    (net (code "62") (name "Net-(U3-RA5)") (class "Default")
      (node (ref "J3") (pin "12") (pinfunction "12_12") (pintype "passive"))
      (node (ref "U3") (pin "61") (pinfunction "RA5_61") (pintype "bidirectional"))
    )
    (net (code "63") (name "Net-(U3-RA7)") (class "Default")
      (node (ref "J4") (pin "18") (pinfunction "18_18") (pintype "passive"))
      (node (ref "U3") (pin "92") (pinfunction "RA7_92") (pintype "bidirectional"))
    )
    (net (code "64") (name "Net-(U3-RC13)") (class "Default")
      (node (ref "J3") (pin "24") (pinfunction "24_24") (pintype "passive"))
      (node (ref "U3") (pin "73") (pinfunction "RC13_73") (pintype "bidirectional"))
    )
    (net (code "65") (name "Net-(U3-RD5)") (class "Default")
      (node (ref "J4") (pin "8") (pinfunction "8_8") (pintype "passive"))
      (node (ref "U3") (pin "82") (pinfunction "RD5_82") (pintype "bidirectional"))
    )
    (net (code "66") (name "Net-(U3-RD6)") (class "Default")
      (node (ref "J4") (pin "7") (pinfunction "7_7") (pintype "passive"))
      (node (ref "U3") (pin "83") (pinfunction "RD6_83") (pintype "bidirectional"))
    )
    (net (code "67") (name "Net-(U3-RD7)") (class "Default")
      (node (ref "J4") (pin "10") (pinfunction "10_10") (pintype "passive"))
      (node (ref "U3") (pin "84") (pinfunction "RD7_84") (pintype "bidirectional"))
    )
    (net (code "68") (name "Net-(U3-RD9)") (class "Default")
      (node (ref "J3") (pin "20") (pinfunction "20_20") (pintype "passive"))
      (node (ref "U3") (pin "69") (pinfunction "RD9_69") (pintype "bidirectional"))
    )
    (net (code "69") (name "Net-(U3-RD11)") (class "Default")
      (node (ref "J3") (pin "22") (pinfunction "22_22") (pintype "passive"))
      (node (ref "U3") (pin "71") (pinfunction "RD11_71") (pintype "bidirectional"))
    )
    (net (code "70") (name "Net-(U3-RD12)") (class "Default")
      (node (ref "J4") (pin "3") (pinfunction "3_3") (pintype "passive"))
      (node (ref "U3") (pin "79") (pinfunction "RD12_79") (pintype "bidirectional"))
    )
    (net (code "71") (name "Net-(U3-RD13)") (class "Default")
      (node (ref "J4") (pin "6") (pinfunction "6_6") (pintype "passive"))
      (node (ref "U3") (pin "80") (pinfunction "RD13_80") (pintype "bidirectional"))
    )
    (net (code "72") (name "Net-(U3-RE1)") (class "Default")
      (node (ref "J4") (pin "20") (pinfunction "20_20") (pintype "passive"))
      (node (ref "U3") (pin "94") (pinfunction "RE1_94") (pintype "bidirectional"))
    )
    (net (code "73") (name "Net-(U3-RE2)") (class "Default")
      (node (ref "J4") (pin "24") (pinfunction "24_24") (pintype "passive"))
      (node (ref "U3") (pin "98") (pinfunction "RE2_98") (pintype "bidirectional"))
    )
    (net (code "74") (name "Net-(U3-RE5)") (class "Default")
      (node (ref "J1") (pin "4") (pinfunction "4_4") (pintype "passive"))
      (node (ref "U3") (pin "3") (pinfunction "RE5_3") (pintype "bidirectional"))
    )
    (net (code "75") (name "Net-(U3-RE6)") (class "Default")
      (node (ref "J1") (pin "3") (pinfunction "3_3") (pintype "passive"))
      (node (ref "R3") (pin "2") (pinfunction "2_2") (pintype "passive"))
      (node (ref "U3") (pin "4") (pinfunction "RE6_4") (pintype "bidirectional"))
    )
    (net (code "76") (name "Net-(U3-RE7)") (class "Default")
      (node (ref "J1") (pin "6") (pinfunction "6_6") (pintype "passive"))
      (node (ref "U3") (pin "5") (pinfunction "RE7_5") (pintype "bidirectional"))
    )
    (net (code "77") (name "Net-(U3-RE8)") (class "Default")
      (node (ref "J1") (pin "17") (pinfunction "17_17") (pintype "passive"))
      (node (ref "U3") (pin "18") (pinfunction "RE8_18") (pintype "bidirectional"))
    )
    (net (code "78") (name "Net-(U3-RE9)") (class "Default")
      (node (ref "J1") (pin "20") (pinfunction "20_20") (pintype "passive"))
      (node (ref "U3") (pin "19") (pinfunction "RE9_19") (pintype "bidirectional"))
    )
    (net (code "79") (name "Net-(U3-RF1)") (class "Default")
      (node (ref "J4") (pin "14") (pinfunction "14_14") (pintype "passive"))
      (node (ref "U3") (pin "88") (pinfunction "RF1_88") (pintype "bidirectional"))
    )
    (net (code "80") (name "Net-(U3-RF3)") (class "Default")
      (node (ref "J3") (pin "2") (pinfunction "2_2") (pintype "passive"))
      (node (ref "U3") (pin "51") (pinfunction "RF3_51") (pintype "bidirectional"))
    )
    (net (code "81") (name "Net-(U3-RG0)") (class "Default")
      (node (ref "J4") (pin "16") (pinfunction "16_16") (pintype "passive"))
      (node (ref "U3") (pin "90") (pinfunction "RG0_90") (pintype "bidirectional"))
    )
    (net (code "82") (name "Net-(U3-RG12)") (class "Default")
      (node (ref "J4") (pin "22") (pinfunction "22_22") (pintype "passive"))
      (node (ref "U3") (pin "96") (pinfunction "RG12_96") (pintype "bidirectional"))
    )
    (net (code "83") (name "Net-(U3-SCK1{slash}RD10)") (class "Default")
      (node (ref "J3") (pin "19") (pinfunction "19_19") (pintype "passive"))
      (node (ref "U3") (pin "70") (pinfunction "SCK1/RD10_70") (pintype "bidirectional"))
    )
    (net (code "84") (name "Net-(U3-SDO1{slash}OC1{slash}RD0)") (class "Default")
      (node (ref "J3") (pin "21") (pinfunction "21_21") (pintype "passive"))
      (node (ref "U3") (pin "72") (pinfunction "SDO1/OC1/RD0_72") (pintype "bidirectional"))
    )
    (net (code "85") (name "Net-(U3-T1CK{slash}RC14)") (class "Default")
      (node (ref "J3") (pin "23") (pinfunction "23_23") (pintype "passive"))
      (node (ref "U3") (pin "74") (pinfunction "T1CK/RC14_74") (pintype "bidirectional"))
    )
    (net (code "86") (name "Net-(U3-T2CK{slash}RC1)") (class "Default")
      (node (ref "J1") (pin "5") (pinfunction "5_5") (pintype "passive"))
      (node (ref "U3") (pin "6") (pinfunction "T2CK/RC1_6") (pintype "bidirectional"))
    )
    (net (code "87") (name "Net-(U3-T3CK{slash}RC2)") (class "Default")
      (node (ref "J1") (pin "8") (pinfunction "8_8") (pintype "passive"))
      (node (ref "U3") (pin "7") (pinfunction "T3CK/RC2_7") (pintype "bidirectional"))
    )
    (net (code "88") (name "Net-(U3-T4CK{slash}RC3)") (class "Default")
      (node (ref "J1") (pin "7") (pinfunction "7_7") (pintype "passive"))
      (node (ref "U3") (pin "8") (pinfunction "T4CK/RC3_8") (pintype "bidirectional"))
    )
    (net (code "89") (name "Net-(U3-USBD+)") (class "Default")
      (node (ref "J7") (pin "D+") (pinfunction "D+_D+") (pintype "bidirectional"))
      (node (ref "U3") (pin "57") (pinfunction "USBD+_57") (pintype "bidirectional"))
    )
    (net (code "90") (name "Net-(U3-USBD-)") (class "Default")
      (node (ref "J7") (pin "D-") (pinfunction "D-_D-") (pintype "bidirectional"))
      (node (ref "U3") (pin "56") (pinfunction "USBD-_56") (pintype "bidirectional"))
    )
    (net (code "91") (name "Net-(U3-VBUS)") (class "Default")
      (node (ref "C19") (pin "1") (pinfunction "1_1") (pintype "passive"))
      (node (ref "J7") (pin "VBUS") (pinfunction "VBUS_VBUS") (pintype "bidirectional"))
      (node (ref "U3") (pin "54") (pinfunction "VBUS_54") (pintype "bidirectional"))
    )
    (net (code "92") (name "Net-(U3-VREF+{slash}RA10)") (class "Default")
      (node (ref "J2") (pin "3") (pinfunction "3_3") (pintype "passive"))
      (node (ref "U3") (pin "29") (pinfunction "VREF+/RA10_29") (pintype "bidirectional"))
    )
    (net (code "93") (name "Net-(U3-VREF-{slash}RA9)") (class "Default")
      (node (ref "J2") (pin "4") (pinfunction "4_4") (pintype "passive"))
      (node (ref "U3") (pin "28") (pinfunction "VREF-/RA9_28") (pintype "bidirectional"))
    )
    (net (code "94") (name "Net-(U4-A)") (class "Default")
      (node (ref "J12") (pin "2") (pinfunction "2_2") (pintype "bidirectional"))
      (node (ref "R6") (pin "1") (pinfunction "1_1") (pintype "passive"))
      (node (ref "U4") (pin "6") (pinfunction "A_6") (pintype "bidirectional"))
    )
    (net (code "95") (name "Net-(U4-B)") (class "Default")
      (node (ref "J12") (pin "1") (pinfunction "1_1") (pintype "bidirectional"))
      (node (ref "R6") (pin "2") (pinfunction "2_2") (pintype "passive"))
      (node (ref "U4") (pin "7") (pinfunction "B_7") (pintype "bidirectional"))
    )
    (net (code "96") (name "unconnected-(J1-Pad25)") (class "Default")
      (node (ref "J1") (pin "25") (pinfunction "25_25") (pintype "passive"))
    )
    (net (code "97") (name "unconnected-(J1-Pad26)") (class "Default")
      (node (ref "J1") (pin "26") (pinfunction "26_26") (pintype "passive"))
    )
    (net (code "98") (name "unconnected-(J7-PadS1)") (class "Default")
      (node (ref "J7") (pin "S1") (pinfunction "S1_S1") (pintype "bidirectional"))
    )
    (net (code "99") (name "unconnected-(J7-PadS2)") (class "Default")
      (node (ref "J7") (pin "S2") (pinfunction "S2_S2") (pintype "bidirectional"))
    )
    (net (code "100") (name "unconnected-(J9-Pad6)") (class "Default")
      (node (ref "J9") (pin "6") (pinfunction "6_6") (pintype "passive"))
    )
    (net (code "101") (name "unconnected-(U2-D1-Pad9)") (class "Default")
      (node (ref "U2") (pin "9") (pinfunction "D1_9") (pintype "bidirectional"))
    )
    (net (code "102") (name "unconnected-(U2-D2-Pad8)") (class "Default")
      (node (ref "U2") (pin "8") (pinfunction "D2_8") (pintype "bidirectional"))
    )
  )
)
